# Main.net
KiCad netlist of a schematic drawn in Altium Designer
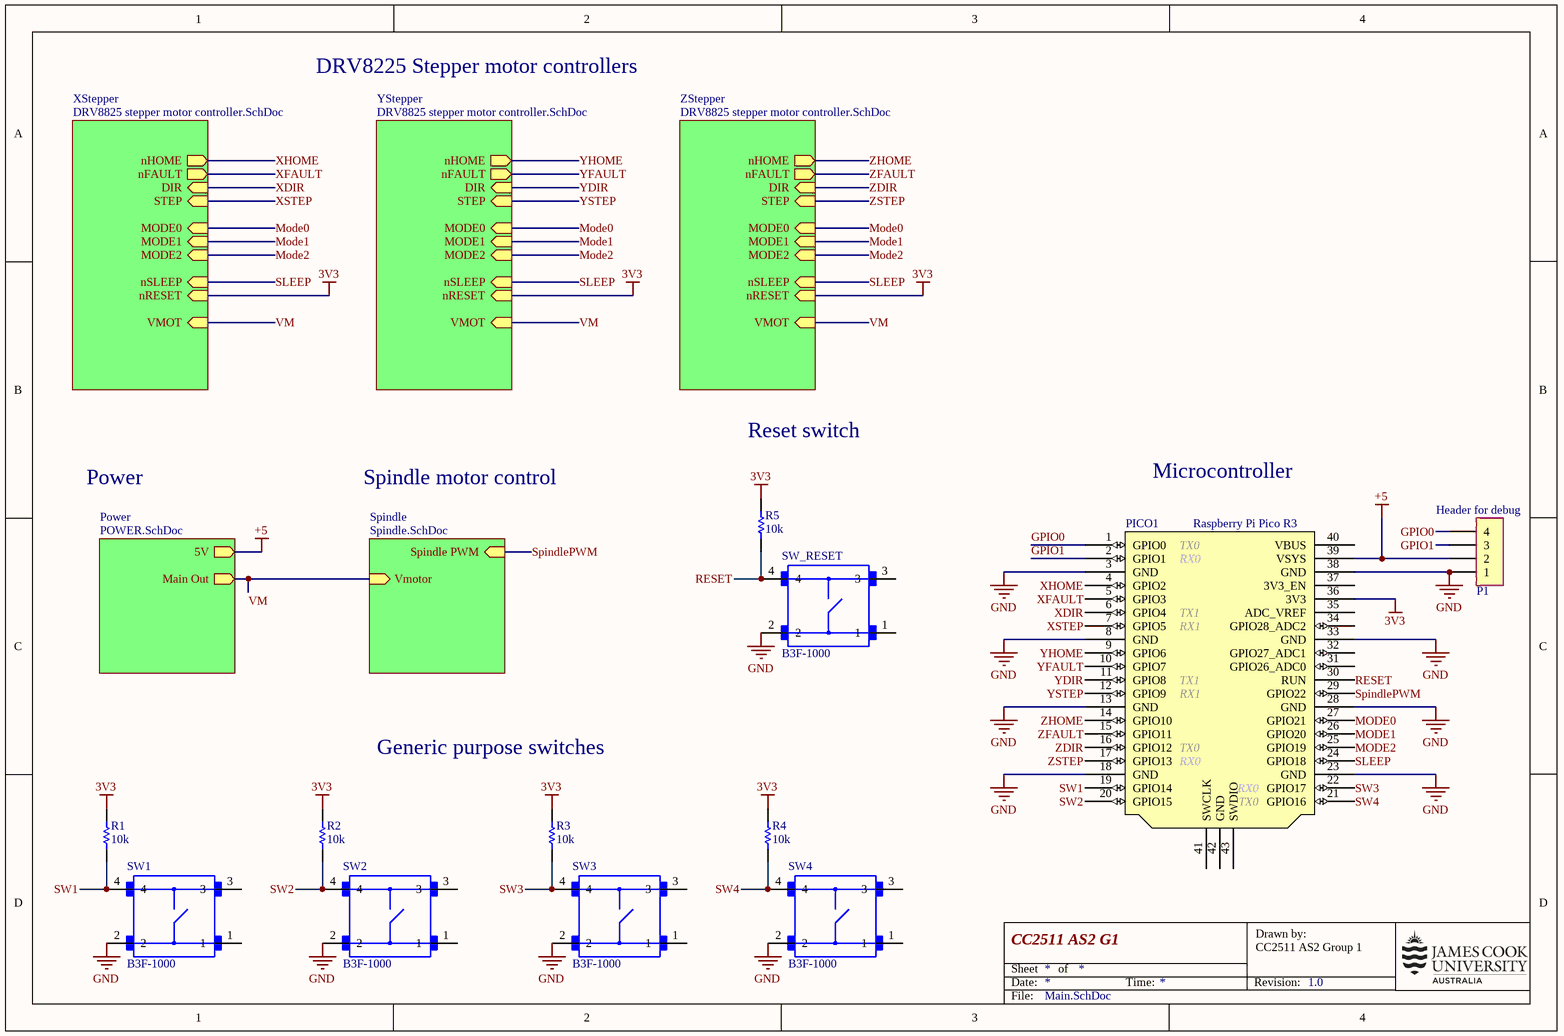
[diagram p0: Main.SchDoc]

(export (version "E")
  (design (tool "Eeschema 10.0.6"))
  (components
    (comp (ref "P1")
      (value "Header for debug")
      (footprint "B4B-XH-A (LF)(SN)")
      (description "Wire-to-board connector, vertical, 2.5mm, 4 contacts")
      (libsource (lib "JCULibrary_AS2_v2") (part "B4B-XH-A (LF)(SN) Wire-to-board connector"))
    )
    (comp (ref "PICO1")
      (value "Raspberry Pi Pico R3")
      (footprint "RASPI_PICO_83")
      (libsource (lib "JCULibrary_AS2_v2") (part "Rapberry Pi Pico-R3"))
    )
    (comp (ref "R1")
      (value "10k")
      (footprint "RESC2013X60X35ML10T20")
      (description "Chip Resistor, 10 KOhm, +/- 5%, 0.125 W, -55 to 155 degC, 0805 (2012 Metric), RoHS, Tape and Reel")
      (fields (field (name "MANUFACTURER") "Yageo"))
      (libsource (lib "Altium Content Vault") (part "RES-2"))
    )
    (comp (ref "R2")
      (value "10k")
      (footprint "RESC2013X60X35ML10T20")
      (description "Chip Resistor, 10 KOhm, +/- 5%, 0.125 W, -55 to 155 degC, 0805 (2012 Metric), RoHS, Tape and Reel")
      (fields (field (name "MANUFACTURER") "Yageo"))
      (libsource (lib "Altium Content Vault") (part "RES-2"))
    )
    (comp (ref "R3")
      (value "10k")
      (footprint "RESC2013X60X35ML10T20")
      (description "Chip Resistor, 10 KOhm, +/- 5%, 0.125 W, -55 to 155 degC, 0805 (2012 Metric), RoHS, Tape and Reel")
      (fields (field (name "MANUFACTURER") "Yageo"))
      (libsource (lib "Altium Content Vault") (part "RES-2"))
    )
    (comp (ref "R4")
      (value "10k")
      (footprint "RESC2013X60X35ML10T20")
      (description "Chip Resistor, 10 KOhm, +/- 5%, 0.125 W, -55 to 155 degC, 0805 (2012 Metric), RoHS, Tape and Reel")
      (fields (field (name "MANUFACTURER") "Yageo"))
      (libsource (lib "Altium Content Vault") (part "RES-2"))
    )
    (comp (ref "R5")
      (value "10k")
      (footprint "RESC2013X60X35ML10T20")
      (description "Chip Resistor, 10 KOhm, +/- 5%, 0.125 W, -55 to 155 degC, 0805 (2012 Metric), RoHS, Tape and Reel")
      (fields (field (name "MANUFACTURER") "Yageo"))
      (libsource (lib "Altium Content Vault") (part "RES-2"))
    )
    (comp (ref "SW1")
      (value "B3F-1000")
      (footprint "SW_B3F-1000")
      (description "Switch Tactile N.O. SPST Flat Round Button PC Pins 0.05A 24VDC 1000000Cycles 0.98N Thru-Hole Bag")
      (fields (field (name "MF") "Omron"))
      (libsource (lib "JCULibrary") (part "B3F-1000"))
    )
    (comp (ref "SW2")
      (value "B3F-1000")
      (footprint "SW_B3F-1000")
      (description "Switch Tactile N.O. SPST Flat Round Button PC Pins 0.05A 24VDC 1000000Cycles 0.98N Thru-Hole Bag")
      (fields (field (name "MF") "Omron"))
      (libsource (lib "JCULibrary") (part "B3F-1000"))
    )
    (comp (ref "SW3")
      (value "B3F-1000")
      (footprint "SW_B3F-1000")
      (description "Switch Tactile N.O. SPST Flat Round Button PC Pins 0.05A 24VDC 1000000Cycles 0.98N Thru-Hole Bag")
      (fields (field (name "MF") "Omron"))
      (libsource (lib "JCULibrary") (part "B3F-1000"))
    )
    (comp (ref "SW4")
      (value "B3F-1000")
      (footprint "SW_B3F-1000")
      (description "Switch Tactile N.O. SPST Flat Round Button PC Pins 0.05A 24VDC 1000000Cycles 0.98N Thru-Hole Bag")
      (fields (field (name "MF") "Omron"))
      (libsource (lib "JCULibrary") (part "B3F-1000"))
    )
    (comp (ref "SW_RESET")
      (value "B3F-1000")
      (footprint "SW_B3F-1000")
      (description "Switch Tactile N.O. SPST Flat Round Button PC Pins 0.05A 24VDC 1000000Cycles 0.98N Thru-Hole Bag")
      (fields (field (name "MF") "Omron"))
      (libsource (lib "JCULibrary") (part "B3F-1000"))
    )
  )
  (nets
    (net (code "1") (name "+5") (class "Default")
      (node (ref "P1") (pin "2") (pinfunction "2_2") (pintype "passive"))
      (node (ref "PICO1") (pin "39") (pinfunction "VSYS_39") (pintype "power_in"))
    )
    (net (code "2") (name "/GPIO0") (class "Default")
      (node (ref "P1") (pin "4") (pinfunction "4_4") (pintype "passive"))
      (node (ref "PICO1") (pin "1") (pinfunction "GPIO0_1") (pintype "bidirectional"))
    )
    (net (code "3") (name "/GPIO1") (class "Default")
      (node (ref "P1") (pin "3") (pinfunction "3_3") (pintype "passive"))
      (node (ref "PICO1") (pin "2") (pinfunction "GPIO1_2") (pintype "bidirectional"))
    )
    (net (code "4") (name "/MODE0") (class "Default")
      (node (ref "PICO1") (pin "27") (pinfunction "GPIO21_27") (pintype "bidirectional"))
    )
    (net (code "5") (name "/MODE1") (class "Default")
      (node (ref "PICO1") (pin "26") (pinfunction "GPIO20_26") (pintype "bidirectional"))
    )
    (net (code "6") (name "/MODE2") (class "Default")
      (node (ref "PICO1") (pin "25") (pinfunction "GPIO19_25") (pintype "bidirectional"))
    )
    (net (code "10") (name "/RESET") (class "Default")
      (node (ref "PICO1") (pin "30") (pinfunction "RUN_30") (pintype "passive"))
      (node (ref "R5") (pin "2") (pinfunction "2_2") (pintype "passive"))
      (node (ref "SW_RESET") (pin "4") (pinfunction "4_4") (pintype "passive"))
    )
    (net (code "11") (name "/SLEEP") (class "Default")
      (node (ref "PICO1") (pin "24") (pinfunction "GPIO18_24") (pintype "bidirectional"))
    )
    (net (code "12") (name "/SW1") (class "Default")
      (node (ref "PICO1") (pin "19") (pinfunction "GPIO14_19") (pintype "bidirectional"))
      (node (ref "R1") (pin "2") (pinfunction "2_2") (pintype "passive"))
      (node (ref "SW1") (pin "4") (pinfunction "4_4") (pintype "passive"))
    )
    (net (code "13") (name "/SW2") (class "Default")
      (node (ref "PICO1") (pin "20") (pinfunction "GPIO15_20") (pintype "bidirectional"))
      (node (ref "R2") (pin "2") (pinfunction "2_2") (pintype "passive"))
      (node (ref "SW2") (pin "4") (pinfunction "4_4") (pintype "passive"))
    )
    (net (code "14") (name "/SW3") (class "Default")
      (node (ref "PICO1") (pin "22") (pinfunction "GPIO17_22") (pintype "bidirectional"))
      (node (ref "R3") (pin "2") (pinfunction "2_2") (pintype "passive"))
      (node (ref "SW3") (pin "4") (pinfunction "4_4") (pintype "passive"))
    )
    (net (code "15") (name "/SW4") (class "Default")
      (node (ref "PICO1") (pin "21") (pinfunction "GPIO16_21") (pintype "bidirectional"))
      (node (ref "R4") (pin "2") (pinfunction "2_2") (pintype "passive"))
      (node (ref "SW4") (pin "4") (pinfunction "4_4") (pintype "passive"))
    )
    (net (code "16") (name "/SpindlePWM") (class "Default")
      (node (ref "PICO1") (pin "29") (pinfunction "GPIO22_29") (pintype "bidirectional"))
    )
    (net (code "18") (name "/XDIR") (class "Default")
      (node (ref "PICO1") (pin "6") (pinfunction "GPIO4_6") (pintype "bidirectional"))
    )
    (net (code "19") (name "/XFAULT") (class "Default")
      (node (ref "PICO1") (pin "5") (pinfunction "GPIO3_5") (pintype "bidirectional"))
    )
    (net (code "20") (name "/XHOME") (class "Default")
      (node (ref "PICO1") (pin "4") (pinfunction "GPIO2_4") (pintype "bidirectional"))
    )
    (net (code "21") (name "/XSTEP") (class "Default")
      (node (ref "PICO1") (pin "7") (pinfunction "GPIO5_7") (pintype "bidirectional"))
    )
    (net (code "22") (name "/YDIR") (class "Default")
      (node (ref "PICO1") (pin "11") (pinfunction "GPIO8_11") (pintype "bidirectional"))
    )
    (net (code "23") (name "/YFAULT") (class "Default")
      (node (ref "PICO1") (pin "10") (pinfunction "GPIO7_10") (pintype "bidirectional"))
    )
    (net (code "24") (name "/YHOME") (class "Default")
      (node (ref "PICO1") (pin "9") (pinfunction "GPIO6_9") (pintype "bidirectional"))
    )
    (net (code "25") (name "/YSTEP") (class "Default")
      (node (ref "PICO1") (pin "12") (pinfunction "GPIO9_12") (pintype "bidirectional"))
    )
    (net (code "26") (name "/ZDIR") (class "Default")
      (node (ref "PICO1") (pin "16") (pinfunction "GPIO12_16") (pintype "bidirectional"))
    )
    (net (code "27") (name "/ZFAULT") (class "Default")
      (node (ref "PICO1") (pin "15") (pinfunction "GPIO11_15") (pintype "bidirectional"))
    )
    (net (code "28") (name "/ZHOME") (class "Default")
      (node (ref "PICO1") (pin "14") (pinfunction "GPIO10_14") (pintype "bidirectional"))
    )
    (net (code "29") (name "/ZSTEP") (class "Default")
      (node (ref "PICO1") (pin "17") (pinfunction "GPIO13_17") (pintype "bidirectional"))
    )
    (net (code "30") (name "3V3") (class "Default")
      (node (ref "PICO1") (pin "36") (pinfunction "3V3_36") (pintype "power_in"))
      (node (ref "R1") (pin "1") (pinfunction "1_1") (pintype "passive"))
      (node (ref "R2") (pin "1") (pinfunction "1_1") (pintype "passive"))
      (node (ref "R3") (pin "1") (pinfunction "1_1") (pintype "passive"))
      (node (ref "R4") (pin "1") (pinfunction "1_1") (pintype "passive"))
      (node (ref "R5") (pin "1") (pinfunction "1_1") (pintype "passive"))
    )
    (net (code "31") (name "GND") (class "Default")
      (node (ref "P1") (pin "1") (pinfunction "1_1") (pintype "passive"))
      (node (ref "PICO1") (pin "13") (pinfunction "GND_13") (pintype "power_in"))
      (node (ref "PICO1") (pin "18") (pinfunction "GND_18") (pintype "power_in"))
      (node (ref "PICO1") (pin "23") (pinfunction "GND_23") (pintype "power_in"))
      (node (ref "PICO1") (pin "28") (pinfunction "GND_28") (pintype "power_in"))
      (node (ref "PICO1") (pin "3") (pinfunction "GND_3") (pintype "power_in"))
      (node (ref "PICO1") (pin "33") (pinfunction "GND_33") (pintype "power_in"))
      (node (ref "PICO1") (pin "38") (pinfunction "GND_38") (pintype "power_in"))
      (node (ref "PICO1") (pin "8") (pinfunction "GND_8") (pintype "power_in"))
      (node (ref "SW1") (pin "2") (pinfunction "2_2") (pintype "passive"))
      (node (ref "SW2") (pin "2") (pinfunction "2_2") (pintype "passive"))
      (node (ref "SW3") (pin "2") (pinfunction "2_2") (pintype "passive"))
      (node (ref "SW4") (pin "2") (pinfunction "2_2") (pintype "passive"))
      (node (ref "SW_RESET") (pin "2") (pinfunction "2_2") (pintype "passive"))
    )
    (net (code "32") (name "unconnected-(PICO1-3V3_EN-Pad37)") (class "Default")
      (node (ref "PICO1") (pin "37") (pinfunction "3V3_EN_37") (pintype "power_in"))
    )
    (net (code "33") (name "unconnected-(PICO1-ADC_VREF-Pad35)") (class "Default")
      (node (ref "PICO1") (pin "35") (pinfunction "ADC_VREF_35") (pintype "passive"))
    )
    (net (code "34") (name "unconnected-(PICO1-GND-Pad42)") (class "Default")
      (node (ref "PICO1") (pin "42") (pinfunction "GND_42") (pintype "power_in"))
    )
    (net (code "35") (name "unconnected-(PICO1-GPIO26_ADC0-Pad31)") (class "Default")
      (node (ref "PICO1") (pin "31") (pinfunction "GPIO26_ADC0_31") (pintype "bidirectional"))
    )
    (net (code "36") (name "unconnected-(PICO1-GPIO27_ADC1-Pad32)") (class "Default")
      (node (ref "PICO1") (pin "32") (pinfunction "GPIO27_ADC1_32") (pintype "bidirectional"))
    )
    (net (code "37") (name "unconnected-(PICO1-GPIO28_ADC2-Pad34)") (class "Default")
      (node (ref "PICO1") (pin "34") (pinfunction "GPIO28_ADC2_34") (pintype "bidirectional"))
    )
    (net (code "38") (name "unconnected-(PICO1-SWCLK-Pad41)") (class "Default")
      (node (ref "PICO1") (pin "41") (pinfunction "SWCLK_41") (pintype "passive"))
    )
    (net (code "39") (name "unconnected-(PICO1-SWDIO-Pad43)") (class "Default")
      (node (ref "PICO1") (pin "43") (pinfunction "SWDIO_43") (pintype "passive"))
    )
    (net (code "40") (name "unconnected-(PICO1-VBUS-Pad40)") (class "Default")
      (node (ref "PICO1") (pin "40") (pinfunction "VBUS_40") (pintype "power_in"))
    )
    (net (code "41") (name "unconnected-(SW1-Pad1)") (class "Default")
      (node (ref "SW1") (pin "1") (pinfunction "1_1") (pintype "passive"))
    )
    (net (code "42") (name "unconnected-(SW1-Pad3)") (class "Default")
      (node (ref "SW1") (pin "3") (pinfunction "3_3") (pintype "passive"))
    )
    (net (code "43") (name "unconnected-(SW2-Pad1)") (class "Default")
      (node (ref "SW2") (pin "1") (pinfunction "1_1") (pintype "passive"))
    )
    (net (code "44") (name "unconnected-(SW2-Pad3)") (class "Default")
      (node (ref "SW2") (pin "3") (pinfunction "3_3") (pintype "passive"))
    )
    (net (code "45") (name "unconnected-(SW3-Pad1)") (class "Default")
      (node (ref "SW3") (pin "1") (pinfunction "1_1") (pintype "passive"))
    )
    (net (code "46") (name "unconnected-(SW3-Pad3)") (class "Default")
      (node (ref "SW3") (pin "3") (pinfunction "3_3") (pintype "passive"))
    )
    (net (code "47") (name "unconnected-(SW4-Pad1)") (class "Default")
      (node (ref "SW4") (pin "1") (pinfunction "1_1") (pintype "passive"))
    )
    (net (code "48") (name "unconnected-(SW4-Pad3)") (class "Default")
      (node (ref "SW4") (pin "3") (pinfunction "3_3") (pintype "passive"))
    )
    (net (code "49") (name "unconnected-(SW_RESET-Pad1)") (class "Default")
      (node (ref "SW_RESET") (pin "1") (pinfunction "1_1") (pintype "passive"))
    )
    (net (code "50") (name "unconnected-(SW_RESET-Pad3)") (class "Default")
      (node (ref "SW_RESET") (pin "3") (pinfunction "3_3") (pintype "passive"))
    )
  )
)
